# CAN_Power.net
KiCad netlist of a schematic drawn in EAGLE
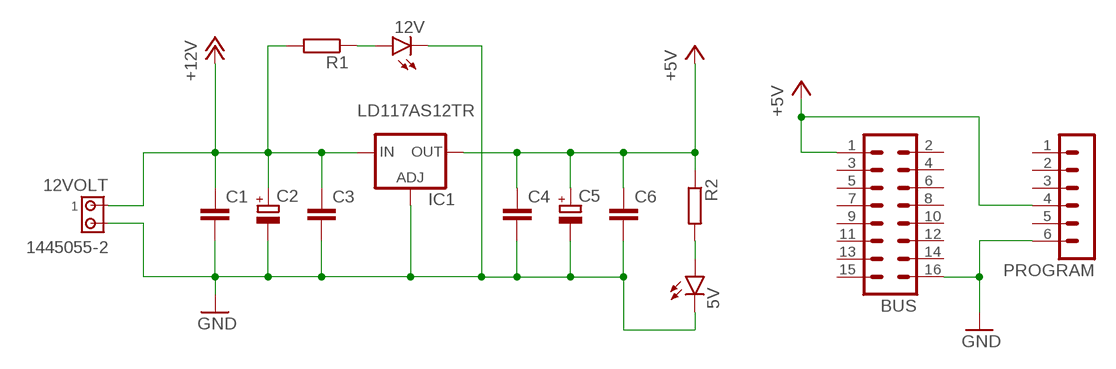
[diagram p0: schematic, sheet 1]

(export (version "E")
  (design (tool "Eeschema 10.0.6"))
  (components
    (comp (ref "5V")
      (value "LED3MM")
      (footprint "eagle-import:LED3MM")
      (libsource (lib "eagle-import") (part "LED3MM"))
    )
    (comp (ref "12V")
      (value "LED3MM")
      (footprint "eagle-import:LED3MM")
      (libsource (lib "eagle-import") (part "LED3MM"))
    )
    (comp (ref "12VOLT")
      (value "1445055-2")
      (footprint "eagle-import:1445055-2")
      (libsource (lib "eagle-import") (part "1445055-2"))
    )
    (comp (ref "BUS")
      (value "MA08-2")
      (footprint "eagle-import:MA08-2")
      (libsource (lib "eagle-import") (part "MA08-2"))
    )
    (comp (ref "C1")
      (value "C-EUC0402")
      (footprint "eagle-import:C0402")
      (libsource (lib "eagle-import") (part "C-EUC0402"))
    )
    (comp (ref "C2")
      (value "CPOL-EUC/6032-28R")
      (footprint "eagle-import:C_6032-28R")
      (libsource (lib "eagle-import") (part "CPOL-EUC/6032-28R"))
    )
    (comp (ref "C3")
      (value "C-EUC0402")
      (footprint "eagle-import:C0402")
      (libsource (lib "eagle-import") (part "C-EUC0402"))
    )
    (comp (ref "C4")
      (value "C-EUC0402")
      (footprint "eagle-import:C0402")
      (libsource (lib "eagle-import") (part "C-EUC0402"))
    )
    (comp (ref "C5")
      (value "CPOL-EUC/6032-28R")
      (footprint "eagle-import:C_6032-28R")
      (libsource (lib "eagle-import") (part "CPOL-EUC/6032-28R"))
    )
    (comp (ref "C6")
      (value "C-EUC0402")
      (footprint "eagle-import:C0402")
      (libsource (lib "eagle-import") (part "C-EUC0402"))
    )
    (comp (ref "IC1")
      (value "LD117AS12TR")
      (footprint "eagle-import:SOT223")
      (libsource (lib "eagle-import") (part "LD117A?S12TR"))
    )
    (comp (ref "PROGRAM")
      (value "MA06-1")
      (footprint "eagle-import:MA06-1")
      (libsource (lib "eagle-import") (part "MA06-1"))
    )
    (comp (ref "R1")
      (value "R-EU_R0402")
      (footprint "eagle-import:R0402")
      (libsource (lib "eagle-import") (part "R-EU_R0402"))
    )
    (comp (ref "R2")
      (value "R-EU_R0402")
      (footprint "eagle-import:R0402")
      (libsource (lib "eagle-import") (part "R-EU_R0402"))
    )
  )
  (nets
    (net (code "1") (name "+5V") (class "Default")
      (node (ref "BUS") (pin "1") (pinfunction "1_1") (pintype "passive"))
      (node (ref "C4") (pin "1") (pinfunction "1_1") (pintype "passive"))
      (node (ref "C5") (pin "+") (pinfunction "+_+") (pintype "passive"))
      (node (ref "C6") (pin "1") (pinfunction "1_1") (pintype "passive"))
      (node (ref "IC1") (pin "4") (pinfunction "OUT_4") (pintype "passive"))
      (node (ref "PROGRAM") (pin "4") (pinfunction "4_4") (pintype "passive"))
      (node (ref "R2") (pin "1") (pinfunction "1_1") (pintype "passive"))
    )
    (net (code "2") (name "+12V") (class "Default")
      (node (ref "12VOLT") (pin "1") (pinfunction "1_1") (pintype "passive"))
      (node (ref "C1") (pin "1") (pinfunction "1_1") (pintype "passive"))
      (node (ref "C2") (pin "+") (pinfunction "+_+") (pintype "passive"))
      (node (ref "C3") (pin "1") (pinfunction "1_1") (pintype "passive"))
      (node (ref "IC1") (pin "3") (pinfunction "IN_3") (pintype "input"))
      (node (ref "R1") (pin "2") (pinfunction "2_2") (pintype "passive"))
    )
    (net (code "3") (name "GND") (class "Default")
      (node (ref "12V") (pin "K") (pinfunction "C_K") (pintype "passive"))
      (node (ref "12VOLT") (pin "2") (pinfunction "2_2") (pintype "passive"))
      (node (ref "5V") (pin "K") (pinfunction "C_K") (pintype "passive"))
      (node (ref "BUS") (pin "16") (pinfunction "16_16") (pintype "passive"))
      (node (ref "C1") (pin "2") (pinfunction "2_2") (pintype "passive"))
      (node (ref "C2") (pin "-") (pinfunction "-_-") (pintype "passive"))
      (node (ref "C3") (pin "2") (pinfunction "2_2") (pintype "passive"))
      (node (ref "C4") (pin "2") (pinfunction "2_2") (pintype "passive"))
      (node (ref "C5") (pin "-") (pinfunction "-_-") (pintype "passive"))
      (node (ref "C6") (pin "2") (pinfunction "2_2") (pintype "passive"))
      (node (ref "IC1") (pin "1") (pinfunction "ADJ_1") (pintype "input"))
      (node (ref "PROGRAM") (pin "6") (pinfunction "6_6") (pintype "passive"))
    )
    (net (code "4") (name "Net-(5V-PadA)") (class "Default")
      (node (ref "5V") (pin "A") (pinfunction "A_A") (pintype "passive"))
      (node (ref "R2") (pin "2") (pinfunction "2_2") (pintype "passive"))
    )
    (net (code "5") (name "Net-(12V-PadA)") (class "Default")
      (node (ref "12V") (pin "A") (pinfunction "A_A") (pintype "passive"))
      (node (ref "R1") (pin "1") (pinfunction "1_1") (pintype "passive"))
    )
    (net (code "6") (name "unconnected-(BUS-Pad2)") (class "Default")
      (node (ref "BUS") (pin "2") (pinfunction "2_2") (pintype "passive"))
    )
    (net (code "7") (name "unconnected-(BUS-Pad3)") (class "Default")
      (node (ref "BUS") (pin "3") (pinfunction "3_3") (pintype "passive"))
    )
    (net (code "8") (name "unconnected-(BUS-Pad4)") (class "Default")
      (node (ref "BUS") (pin "4") (pinfunction "4_4") (pintype "passive"))
    )
    (net (code "9") (name "unconnected-(BUS-Pad5)") (class "Default")
      (node (ref "BUS") (pin "5") (pinfunction "5_5") (pintype "passive"))
    )
    (net (code "10") (name "unconnected-(BUS-Pad6)") (class "Default")
      (node (ref "BUS") (pin "6") (pinfunction "6_6") (pintype "passive"))
    )
    (net (code "11") (name "unconnected-(BUS-Pad7)") (class "Default")
      (node (ref "BUS") (pin "7") (pinfunction "7_7") (pintype "passive"))
    )
    (net (code "12") (name "unconnected-(BUS-Pad8)") (class "Default")
      (node (ref "BUS") (pin "8") (pinfunction "8_8") (pintype "passive"))
    )
    (net (code "13") (name "unconnected-(BUS-Pad9)") (class "Default")
      (node (ref "BUS") (pin "9") (pinfunction "9_9") (pintype "passive"))
    )
    (net (code "14") (name "unconnected-(BUS-Pad10)") (class "Default")
      (node (ref "BUS") (pin "10") (pinfunction "10_10") (pintype "passive"))
    )
    (net (code "15") (name "unconnected-(BUS-Pad11)") (class "Default")
      (node (ref "BUS") (pin "11") (pinfunction "11_11") (pintype "passive"))
    )
    (net (code "16") (name "unconnected-(BUS-Pad12)") (class "Default")
      (node (ref "BUS") (pin "12") (pinfunction "12_12") (pintype "passive"))
    )
    (net (code "17") (name "unconnected-(BUS-Pad13)") (class "Default")
      (node (ref "BUS") (pin "13") (pinfunction "13_13") (pintype "passive"))
    )
    (net (code "18") (name "unconnected-(BUS-Pad14)") (class "Default")
      (node (ref "BUS") (pin "14") (pinfunction "14_14") (pintype "passive"))
    )
    (net (code "19") (name "unconnected-(BUS-Pad15)") (class "Default")
      (node (ref "BUS") (pin "15") (pinfunction "15_15") (pintype "passive"))
    )
    (net (code "20") (name "unconnected-(PROGRAM-Pad1)") (class "Default")
      (node (ref "PROGRAM") (pin "1") (pinfunction "1_1") (pintype "passive"))
    )
    (net (code "21") (name "unconnected-(PROGRAM-Pad2)") (class "Default")
      (node (ref "PROGRAM") (pin "2") (pinfunction "2_2") (pintype "passive"))
    )
    (net (code "22") (name "unconnected-(PROGRAM-Pad3)") (class "Default")
      (node (ref "PROGRAM") (pin "3") (pinfunction "3_3") (pintype "passive"))
    )
    (net (code "23") (name "unconnected-(PROGRAM-Pad5)") (class "Default")
      (node (ref "PROGRAM") (pin "5") (pinfunction "5_5") (pintype "passive"))
    )
  )
)
